# Circuit.net
KiCad netlist of a schematic drawn in Altium Designer
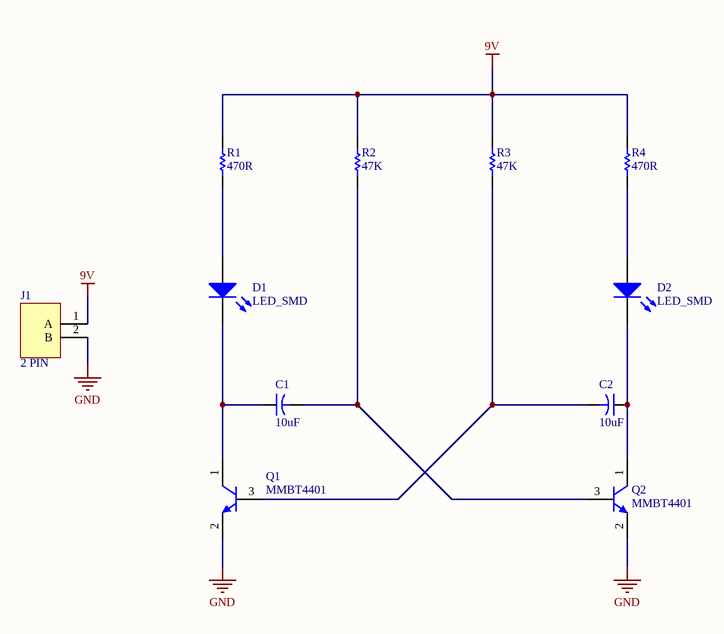
[diagram p0: Circuit.SchDoc]

(export (version "E")
  (design (tool "Eeschema 10.0.6"))
  (components
    (comp (ref "C1")
      (value "10uF")
      (footprint "CAPR5-4X5")
      (description "Capacitor")
      (fields (field (name "Comment") "Cap2"))
      (libsource (lib "Custom_Component") (part "Cap2"))
    )
    (comp (ref "C2")
      (value "10uF")
      (footprint "CAPR5-4X5")
      (description "Capacitor")
      (fields (field (name "Comment") "Cap2"))
      (libsource (lib "Custom_Component") (part "Cap2"))
    )
    (comp (ref "D1")
      (value "LED_SMD")
      (footprint "0603_LED")
      (description "LED RED CLEAR 0603 SMD")
      (fields
        (field (name "DIGIKEY PART NUMBER") "160-1447-1-ND")
        (field (name "MANUFACTURER PART NUMBER") "LTST-C191KRKT")
      )
      (libsource (lib "Custom_Component") (part "LED_SMD"))
    )
    (comp (ref "D2")
      (value "LED_SMD")
      (footprint "0603_LED")
      (description "LED RED CLEAR 0603 SMD")
      (fields
        (field (name "DIGIKEY PART NUMBER") "160-1447-1-ND")
        (field (name "MANUFACTURER PART NUMBER") "LTST-C191KRKT")
      )
      (libsource (lib "Custom_Component") (part "LED_SMD"))
    )
    (comp (ref "J1")
      (value "2 PIN")
      (footprint "JST_2_PIN")
      (libsource (lib "Custom_Component") (part "Connector_2Pin"))
    )
    (comp (ref "Q1")
      (value "MMBT4401")
      (footprint "SOT23_N")
      (description "NPN Bipolar Transistor")
      (fields
        (field (name "DIGIKEY PART NUMBER") "MMBT4401LT1GOSCT-ND")
        (field (name "MANUFACTURER") "ON Semiconductor")
      )
      (libsource (lib "Custom_Component") (part "NPN"))
    )
    (comp (ref "Q2")
      (value "MMBT4401")
      (footprint "SOT23_N")
      (description "NPN Bipolar Transistor")
      (fields
        (field (name "DIGIKEY PART NUMBER") "MMBT4401LT1GOSCT-ND")
        (field (name "MANUFACTURER") "ON Semiconductor")
      )
      (libsource (lib "Custom_Component") (part "NPN"))
    )
    (comp (ref "R1")
      (value "470R")
      (footprint "R0603")
      (description "Resistor")
      (fields (field (name "Comment") "Res1"))
      (libsource (lib "Custom_Component") (part "Res1"))
    )
    (comp (ref "R2")
      (value "47K")
      (footprint "R0603")
      (description "Resistor")
      (fields (field (name "Comment") "Res1"))
      (libsource (lib "Custom_Component") (part "Res1"))
    )
    (comp (ref "R3")
      (value "47K")
      (footprint "R0603")
      (description "Resistor")
      (fields (field (name "Comment") "Res1"))
      (libsource (lib "Custom_Component") (part "Res1"))
    )
    (comp (ref "R4")
      (value "470R")
      (footprint "R0603")
      (description "Resistor")
      (fields (field (name "Comment") "Res1"))
      (libsource (lib "Custom_Component") (part "Res1"))
    )
  )
  (nets
    (net (code "1") (name "9V") (class "Default")
      (node (ref "J1") (pin "1") (pinfunction "A_1") (pintype "passive"))
      (node (ref "R1") (pin "1") (pinfunction "1_1") (pintype "passive"))
      (node (ref "R2") (pin "1") (pinfunction "1_1") (pintype "passive"))
      (node (ref "R3") (pin "1") (pinfunction "1_1") (pintype "passive"))
      (node (ref "R4") (pin "1") (pinfunction "1_1") (pintype "passive"))
    )
    (net (code "2") (name "GND") (class "Default")
      (node (ref "J1") (pin "2") (pinfunction "B_2") (pintype "passive"))
      (node (ref "Q1") (pin "2") (pinfunction "E_2") (pintype "passive"))
      (node (ref "Q2") (pin "2") (pinfunction "E_2") (pintype "passive"))
    )
    (net (code "3") (name "Net-(D1-A)") (class "Default")
      (node (ref "D1") (pin "1") (pinfunction "A_1") (pintype "passive"))
      (node (ref "R1") (pin "2") (pinfunction "2_2") (pintype "passive"))
    )
    (net (code "4") (name "Net-(D1-K)") (class "Default")
      (node (ref "C1") (pin "1") (pinfunction "1_1") (pintype "passive"))
      (node (ref "D1") (pin "2") (pinfunction "K_2") (pintype "passive"))
      (node (ref "Q1") (pin "1") (pinfunction "C_1") (pintype "passive"))
    )
    (net (code "5") (name "Net-(D2-A)") (class "Default")
      (node (ref "D2") (pin "1") (pinfunction "A_1") (pintype "passive"))
      (node (ref "R4") (pin "2") (pinfunction "2_2") (pintype "passive"))
    )
    (net (code "6") (name "Net-(D2-K)") (class "Default")
      (node (ref "C2") (pin "1") (pinfunction "1_1") (pintype "passive"))
      (node (ref "D2") (pin "2") (pinfunction "K_2") (pintype "passive"))
      (node (ref "Q2") (pin "1") (pinfunction "C_1") (pintype "passive"))
    )
    (net (code "7") (name "Net-(Q1-B)") (class "Default")
      (node (ref "C2") (pin "2") (pinfunction "2_2") (pintype "passive"))
      (node (ref "Q1") (pin "3") (pinfunction "B_3") (pintype "passive"))
      (node (ref "R3") (pin "2") (pinfunction "2_2") (pintype "passive"))
    )
    (net (code "8") (name "Net-(Q2-B)") (class "Default")
      (node (ref "C1") (pin "2") (pinfunction "2_2") (pintype "passive"))
      (node (ref "Q2") (pin "3") (pinfunction "B_3") (pintype "passive"))
      (node (ref "R2") (pin "2") (pinfunction "2_2") (pintype "passive"))
    )
  )
)
